# M_dulo_U_V_B_v_1_0.net
KiCad netlist of a schematic drawn in EAGLE
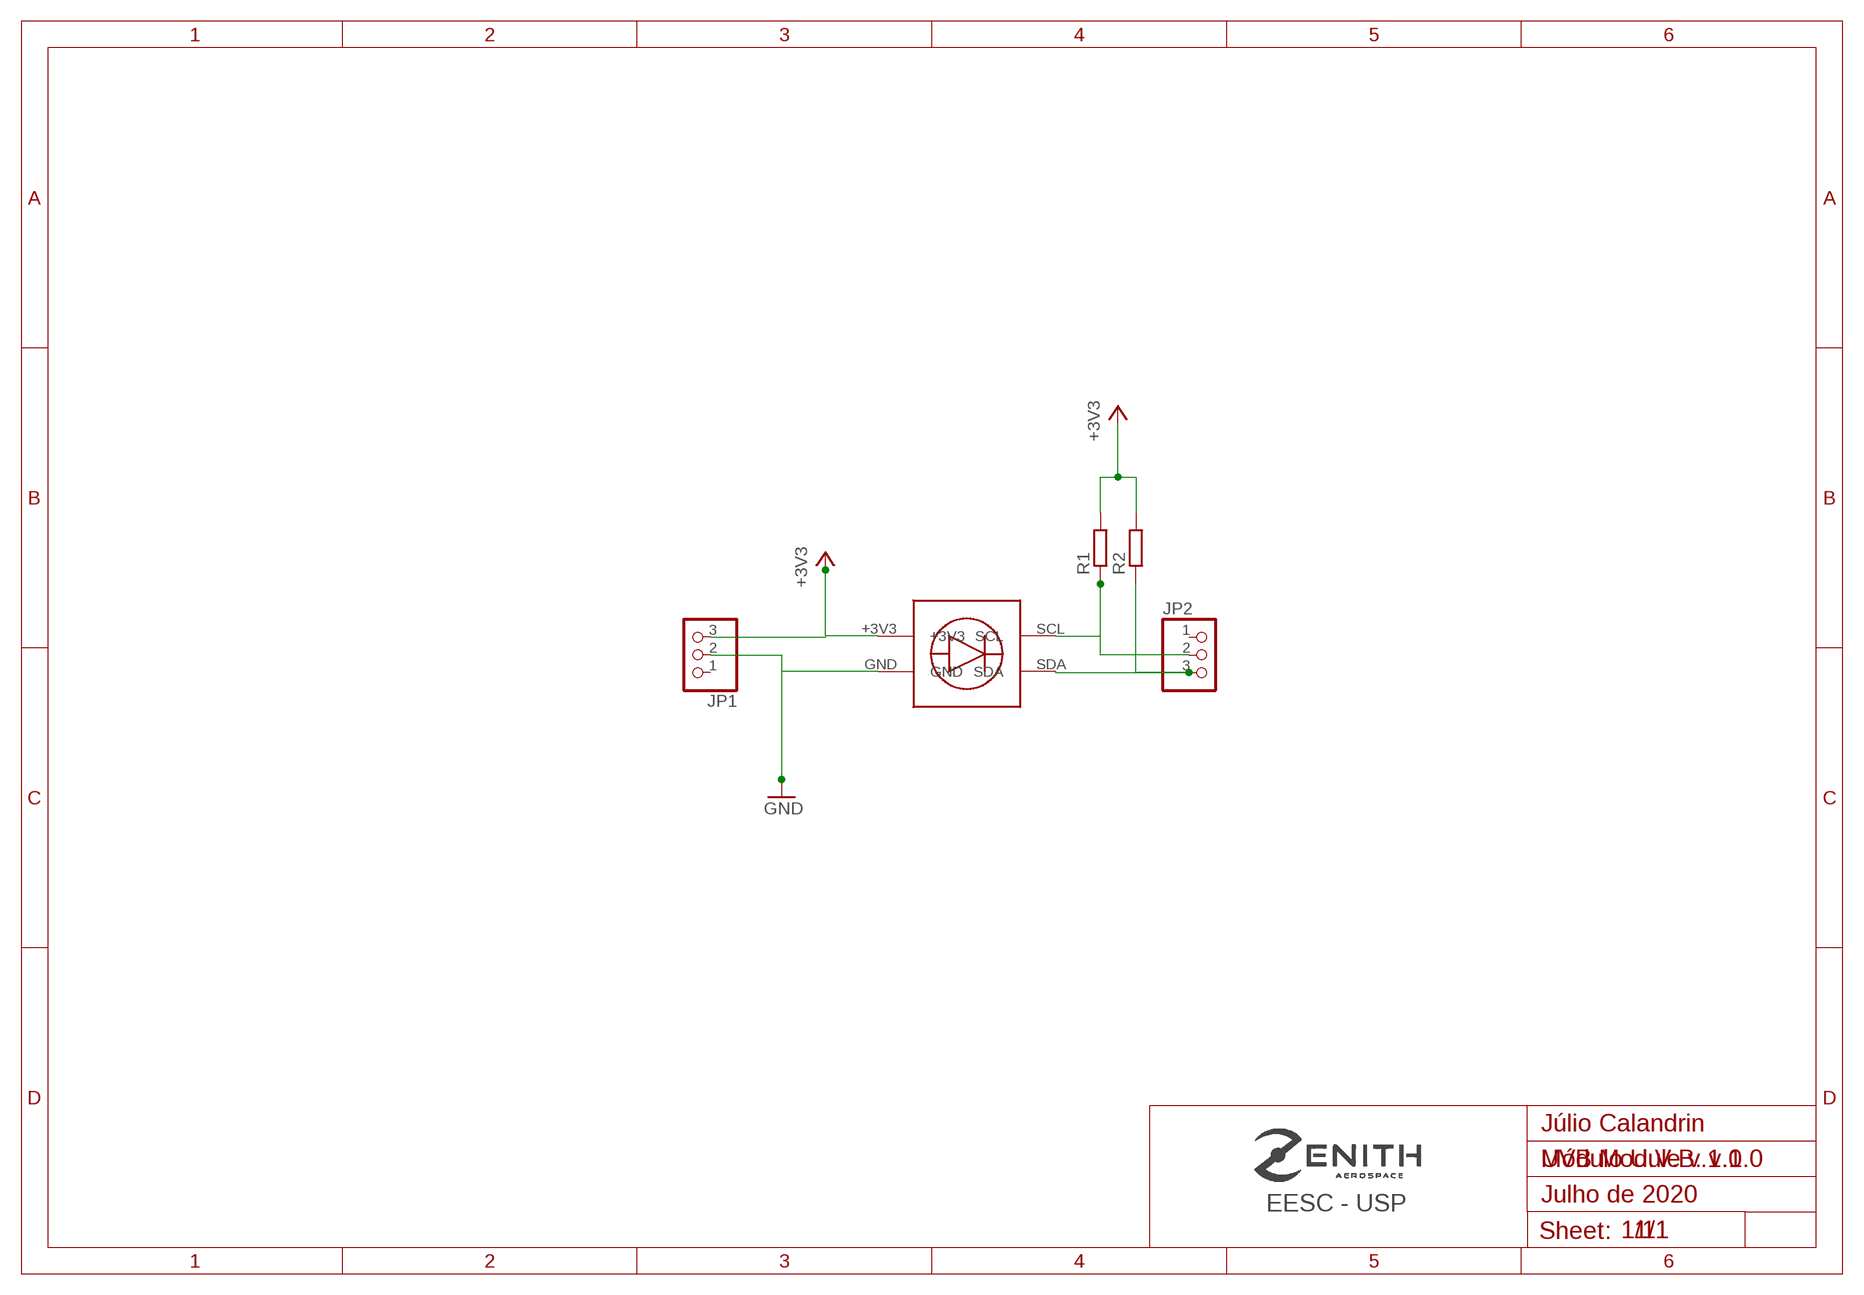
[diagram p0: schematic, sheet 1]

(export (version "E")
  (design (tool "Eeschema 10.0.6"))
  (components
    (comp (ref "JP1")
      (value "PINHD-1X3")
      (footprint "eagle-import:1X03")
      (libsource (lib "eagle-import") (part "PINHD-1X3"))
    )
    (comp (ref "JP2")
      (value "PINHD-1X3")
      (footprint "eagle-import:1X03")
      (libsource (lib "eagle-import") (part "PINHD-1X3"))
    )
    (comp (ref "R1")
      (value "R-EU_R0805")
      (footprint "eagle-import:R0805")
      (libsource (lib "eagle-import") (part "R-EU_R0805"))
    )
    (comp (ref "R2")
      (value "R-EU_R0805")
      (footprint "eagle-import:R0805")
      (libsource (lib "eagle-import") (part "R-EU_R0805"))
    )
    (comp (ref "U$1")
      (value "BREAKOUT_UV-B")
      (footprint "eagle-import:PADS_UV-A_B")
      (libsource (lib "eagle-import") (part "BREAKOUT_UV-B"))
    )
  )
  (nets
    (net (code "1") (name "+3V3") (class "Default")
      (node (ref "JP1") (pin "3") (pinfunction "3_3") (pintype "passive"))
      (node (ref "R1") (pin "2") (pinfunction "2_2") (pintype "passive"))
      (node (ref "R2") (pin "2") (pinfunction "2_2") (pintype "passive"))
      (node (ref "U$1") (pin "+3V3") (pinfunction "+3V3_+3V3") (pintype "bidirectional"))
    )
    (net (code "2") (name "GND") (class "Default")
      (node (ref "JP1") (pin "2") (pinfunction "2_2") (pintype "passive"))
      (node (ref "U$1") (pin "GND") (pinfunction "GND_GND") (pintype "bidirectional"))
    )
    (net (code "3") (name "Net-(JP2-Pad2)") (class "Default")
      (node (ref "JP2") (pin "2") (pinfunction "2_2") (pintype "passive"))
      (node (ref "R1") (pin "1") (pinfunction "1_1") (pintype "passive"))
      (node (ref "U$1") (pin "SCL") (pinfunction "SCL_SCL") (pintype "bidirectional"))
    )
    (net (code "4") (name "Net-(JP2-Pad3)") (class "Default")
      (node (ref "JP2") (pin "3") (pinfunction "3_3") (pintype "passive"))
      (node (ref "R2") (pin "1") (pinfunction "1_1") (pintype "passive"))
      (node (ref "U$1") (pin "SDA") (pinfunction "SDA_SDA") (pintype "bidirectional"))
    )
    (net (code "5") (name "unconnected-(JP1-Pad1)") (class "Default")
      (node (ref "JP1") (pin "1") (pinfunction "1_1") (pintype "passive"))
    )
    (net (code "6") (name "unconnected-(JP2-Pad1)") (class "Default")
      (node (ref "JP2") (pin "1") (pinfunction "1_1") (pintype "passive"))
    )
  )
)
